# Netscale48HD_Power_Supply.net
KiCad netlist of a schematic drawn in Altium Designer
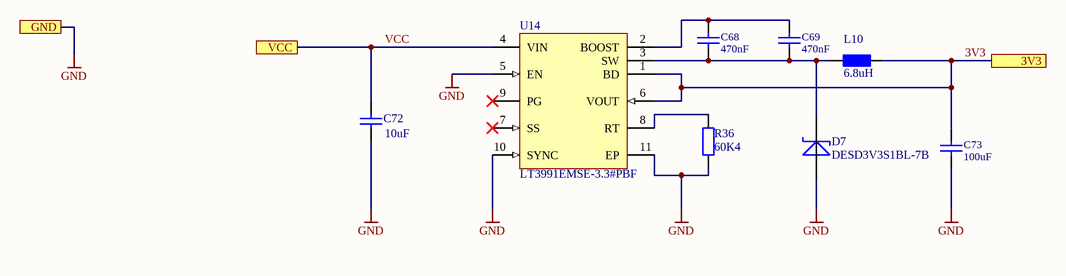
[diagram p0: Netscale48HD_Power_Supply.SchDoc]

(export (version "E")
  (design (tool "Eeschema 10.0.6"))
  (components
    (comp (ref "C68")
      (value "470nF")
      (footprint "CAP-0805[2012] - RFL")
      (description "470nF, 100V, X7R, 10 %, Chip Monolithic Ceramic Capacitor for General, 0805 (metric 2012)")
      (fields (field (name "MANUFACTURER") "Murata") (field (name "VOLTAGE") "100 VDC"))
      (libsource (lib "RDM_ALT_SCH") (part "Cap_470nF_0805_100V"))
    )
    (comp (ref "C69")
      (value "470nF")
      (footprint "CAP-0805[2012] - RFL")
      (description "470nF, 100V, X7R, 10 %, Chip Monolithic Ceramic Capacitor for General, 0805 (metric 2012)")
      (fields (field (name "MANUFACTURER") "Murata") (field (name "VOLTAGE") "100 VDC"))
      (libsource (lib "RDM_ALT_SCH") (part "Cap_470nF_0805_100V"))
    )
    (comp (ref "C72")
      (value "10uF")
      (footprint "CAPC5750X279X64LL40T39")
      (description "Chip Capacitor, 10 uF, +/- 20%, 100 V, -55 to 125 degC, 2220 (5750 Metric), RoHS, Tape and Reel")
      (fields (field (name "MANUFACTURER") "AVX") (field (name "Comment") "22201C106MAT2A"))
      (libsource (lib "RDM_Altium_Library") (part "CMP-2000-07534-1"))
    )
    (comp (ref "C73")
      (value "100uF")
      (footprint "CAP-1210[3225] - RFL")
      (description "Multilayer Ceramic Capacitors MLCC - SMD/SMT 1210 100uF 10volts *Derate Voltage/Temp")
      (fields (field (name "MANUFACTURER") "Murata") (field (name "VOLTAGE") "10 V"))
      (libsource (lib "RDM_ALT_SCH") (part "Cap_100uF_10V_1210"))
    )
    (comp (ref "D7")
      (value "DESD3V3S1BL-7B")
      (footprint "DFN1006-2")
      (description "15MQ060N SCHOTTKY RECTIFIER")
      (fields (field (name "MANUFACTURER") "SMC"))
      (libsource (lib "RDM_Altium_Library") (part "SCHOTTKY-DIODE-1K-2A"))
    )
    (comp (ref "L10")
      (value "78438357068")
      (footprint "Würth_Special Murata LQH5BPN_2_R")
      (description "6.8uH, WE-MAIA SMD Power Inductor")
      (fields (field (name "MANUFACTURER") "Würth") (field (name "SHORTDESCRIPTION") "6.8uH"))
      (libsource (lib "RDM_Altium_Library") (part "SMD power Inductor"))
    )
    (comp (ref "R36")
      (value "60K4")
      (footprint "RES-0402[1005] - RFL")
      (description "60.4 kOhms ±1% 0.063W, 1/16W Chip Resistor 0402 (1005 Metric) Moisture Resistant Thick Film")
      (fields (field (name "TOLERANCE") "1%") (field (name "MANUFACTURER") "Yageo"))
      (libsource (lib "RDM_ALT_SCH") (part "PassResBas0402-00711-A.3"))
    )
    (comp (ref "U14")
      (value "LT3991EMSE-3.3#PBF")
      (footprint "Linear_10-Lead Plastic MSOP_11_R")
      (description "55V, 1.2A Step-Down Regulator with 2.8μA Quiescent Current")
      (fields (field (name "MANUFACTURER") "Linear"))
      (libsource (lib "RDM_Altium_Library") (part "Linear_LT3991-3.3_10-Lead Plastic MSOP_11"))
    )
  )
  (nets
    (net (code "1") (name "/3V3") (class "Default")
      (node (ref "C73") (pin "1") (pinfunction "Pos_1") (pintype "passive"))
      (node (ref "L10") (pin "2") (pinfunction "2_2") (pintype "passive"))
      (node (ref "U14") (pin "1") (pinfunction "BD_1") (pintype "power_in"))
      (node (ref "U14") (pin "6") (pinfunction "VOUT_6") (pintype "input"))
    )
    (net (code "2") (name "/VCC") (class "Default")
      (node (ref "C72") (pin "2") (pinfunction "2_2") (pintype "passive"))
      (node (ref "U14") (pin "4") (pinfunction "VIN_4") (pintype "power_in"))
    )
    (net (code "3") (name "GND") (class "Default")
      (node (ref "C72") (pin "1") (pinfunction "1_1") (pintype "passive"))
      (node (ref "C73") (pin "2") (pinfunction "Neg_2") (pintype "passive"))
      (node (ref "D7") (pin "2") (pinfunction "A_2") (pintype "passive"))
      (node (ref "R36") (pin "2") (pinfunction "2_2") (pintype "passive"))
      (node (ref "U14") (pin "10") (pinfunction "SYNC_10") (pintype "input"))
      (node (ref "U14") (pin "11") (pinfunction "EP_11") (pintype "power_in"))
      (node (ref "U14") (pin "5") (pinfunction "EN_5") (pintype "input"))
    )
    (net (code "4") (name "Net-(C68-Neg)") (class "Default")
      (node (ref "C68") (pin "2") (pinfunction "Neg_2") (pintype "passive"))
      (node (ref "C69") (pin "2") (pinfunction "Neg_2") (pintype "passive"))
      (node (ref "D7") (pin "1") (pinfunction "K_1") (pintype "passive"))
      (node (ref "L10") (pin "1") (pinfunction "1_1") (pintype "passive"))
      (node (ref "U14") (pin "3") (pinfunction "SW_3") (pintype "power_in"))
    )
    (net (code "5") (name "Net-(C68-Pos)") (class "Default")
      (node (ref "C68") (pin "1") (pinfunction "Pos_1") (pintype "passive"))
      (node (ref "C69") (pin "1") (pinfunction "Pos_1") (pintype "passive"))
      (node (ref "U14") (pin "2") (pinfunction "BOOST_2") (pintype "passive"))
    )
    (net (code "6") (name "Net-(U14-RT)") (class "Default")
      (node (ref "R36") (pin "1") (pinfunction "1_1") (pintype "passive"))
      (node (ref "U14") (pin "8") (pinfunction "RT_8") (pintype "passive"))
    )
    (net (code "7") (name "unconnected-(U14-PG-Pad9)") (class "Default")
      (node (ref "U14") (pin "9") (pinfunction "PG_9") (pintype "open_collector+no_connect"))
    )
    (net (code "8") (name "unconnected-(U14-SS-Pad7)") (class "Default")
      (node (ref "U14") (pin "7") (pinfunction "SS_7") (pintype "input+no_connect"))
    )
  )
)
